# Sheet.net
KiCad netlist of a schematic drawn in Altium Designer
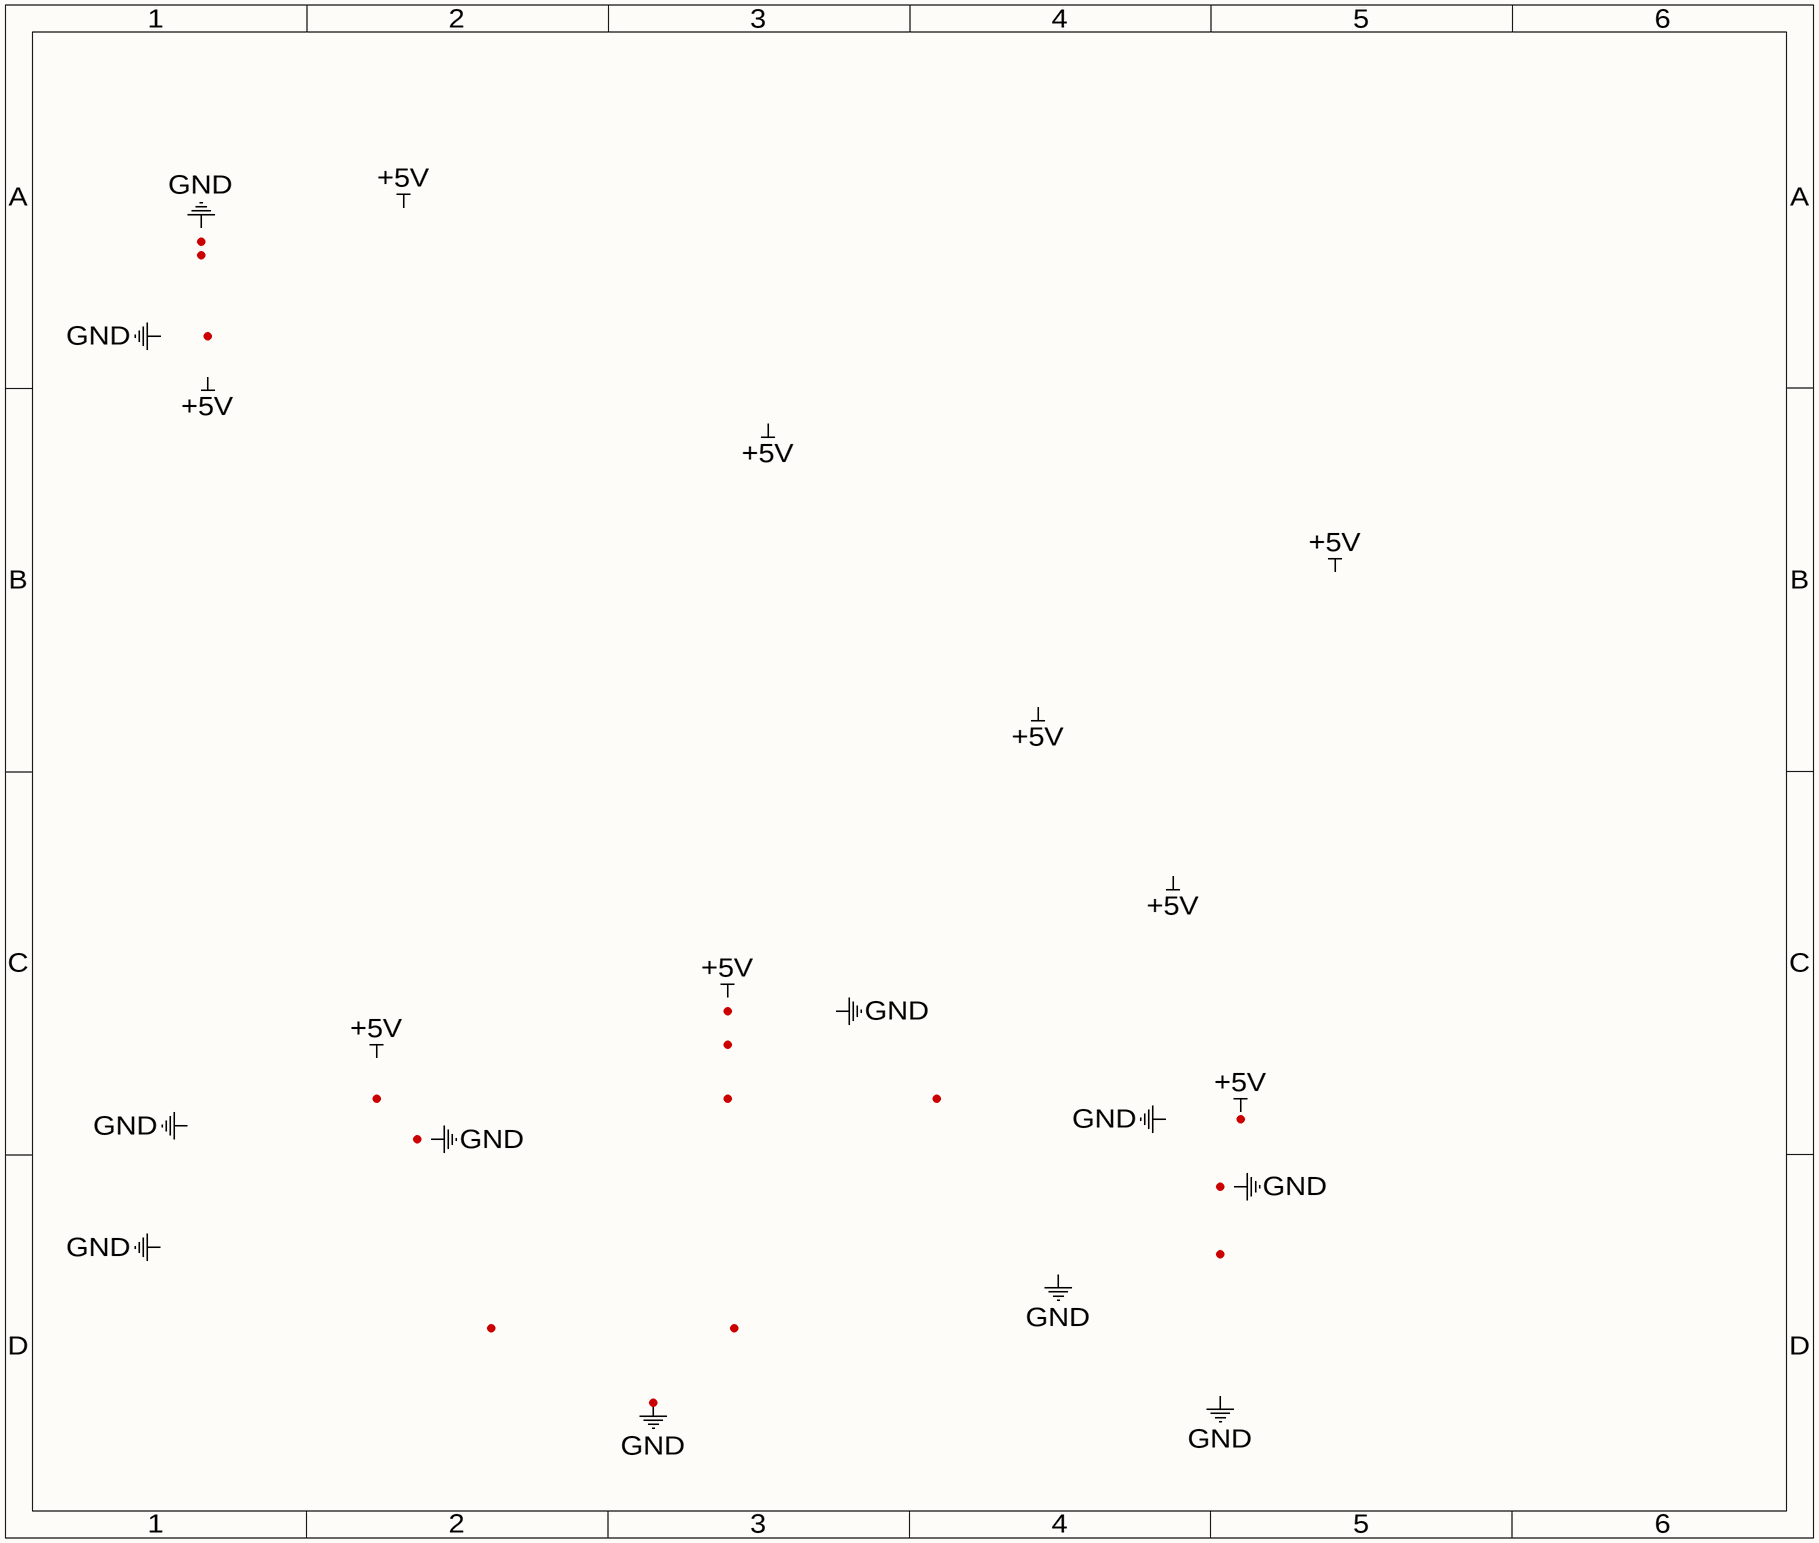
[diagram p0: Sheet.schdoc]

(export (version "E")
  (design (tool "Eeschema 10.0.6"))
  (components
    (comp (ref "BOARD1")
      (value "ESP32DEVKITV1")
      (fields (field (name "CONTRIBUTOR") "radio"))
      (libsource (lib "altium-import") (part "root_0_ESP32DEVKITV1_"))
    )
    (comp (ref "C1")
      (value "100nF")
      (fields
        (field (name "BOM_SUPPLIER PART") "C328914")
        (field (name "BOM_MANUFACTURER PART") "FN15X104K160PNG")
        (field (name "CONTRIBUTOR") "LCSC")
      )
      (libsource (lib "altium-import") (part "root_2_100nF_"))
    )
    (comp (ref "C2")
      (value "100nF")
      (fields
        (field (name "BOM_SUPPLIER PART") "C328914")
        (field (name "BOM_MANUFACTURER PART") "FN15X104K160PNG")
        (field (name "CONTRIBUTOR") "LCSC")
      )
      (libsource (lib "altium-import") (part "root_2_100nF_"))
    )
    (comp (ref "C3")
      (value "100nF")
      (fields
        (field (name "BOM_SUPPLIER PART") "C328914")
        (field (name "BOM_MANUFACTURER PART") "FN15X104K160PNG")
        (field (name "CONTRIBUTOR") "LCSC")
      )
      (libsource (lib "altium-import") (part "root_1_100nF_"))
    )
    (comp (ref "C4")
      (value "100nF")
      (fields
        (field (name "BOM_SUPPLIER PART") "C328914")
        (field (name "BOM_MANUFACTURER PART") "FN15X104K160PNG")
        (field (name "CONTRIBUTOR") "LCSC")
      )
      (libsource (lib "altium-import") (part "root_3_100nF_"))
    )
    (comp (ref "C5")
      (value "100nF")
      (fields
        (field (name "BOM_SUPPLIER PART") "C328914")
        (field (name "BOM_MANUFACTURER PART") "FN15X104K160PNG")
        (field (name "CONTRIBUTOR") "LCSC")
      )
      (libsource (lib "altium-import") (part "root_2_100nF_"))
    )
    (comp (ref "C6")
      (value "100nF")
      (fields
        (field (name "BOM_SUPPLIER PART") "C328914")
        (field (name "BOM_MANUFACTURER PART") "FN15X104K160PNG")
        (field (name "CONTRIBUTOR") "LCSC")
      )
      (libsource (lib "altium-import") (part "root_2_100nF_"))
    )
    (comp (ref "ERROR")
      (value "17-21SURC/S530-A2/TR8")
      (fields (field (name "BOM_SUPPLIER PART") "C131244") (field (name "CONTRIBUTOR") "LCSC"))
      (libsource (lib "altium-import") (part "root_1_17-21SURC/S530-A2/TR8_"))
    )
    (comp (ref "GC")
      (value "17-21SURC/S530-A2/TR8")
      (fields (field (name "BOM_SUPPLIER PART") "C131244") (field (name "CONTRIBUTOR") "LCSC"))
      (libsource (lib "altium-import") (part "root_1_17-21SURC/S530-A2/TR8_"))
    )
    (comp (ref "GL")
      (value "17-21SURC/S530-A2/TR8")
      (fields (field (name "BOM_SUPPLIER PART") "C131244") (field (name "CONTRIBUTOR") "LCSC"))
      (libsource (lib "altium-import") (part "root_1_17-21SURC/S530-A2/TR8_"))
    )
    (comp (ref "GR")
      (value "17-21SURC/S530-A2/TR8")
      (fields (field (name "BOM_SUPPLIER PART") "C131244") (field (name "CONTRIBUTOR") "LCSC"))
      (libsource (lib "altium-import") (part "root_1_17-21SURC/S530-A2/TR8_"))
    )
    (comp (ref "K1")
      (value "KH-3635-CAJ")
      (fields (field (name "BOM_SUPPLIER PART") "C530670") (field (name "CONTRIBUTOR") "LCSC"))
      (libsource (lib "altium-import") (part "root_0_KH-3635-CAJ_"))
    )
    (comp (ref "K2")
      (value "KH-3635-CAJ")
      (fields (field (name "BOM_SUPPLIER PART") "C530670") (field (name "CONTRIBUTOR") "LCSC"))
      (libsource (lib "altium-import") (part "root_0_KH-3635-CAJ_"))
    )
    (comp (ref "LED1")
      (value "17-21SYGC/S530-E3/TR8")
      (fields (field (name "BOM_SUPPLIER PART") "C142303") (field (name "CONTRIBUTOR") "LCSC"))
      (libsource (lib "altium-import") (part "root_1_17-21SYGC/S530-E3/TR8_"))
    )
    (comp (ref "OLED1")
      (value "0.96OLED_4P")
      (fields (field (name "CONTRIBUTOR") "LCEDA_Lib"))
      (libsource (lib "altium-import") (part "root_0_0.96OLED_4P_"))
    )
    (comp (ref "OPEN")
      (value "SK-3296S-01-L1")
      (fields (field (name "BOM_SUPPLIER PART") "C319020") (field (name "CONTRIBUTOR") "LCSC"))
      (libsource (lib "altium-import") (part "root_1_SK-3296S-01-L1_"))
    )
    (comp (ref "R1")
      (value "510")
      (fields
        (field (name "BOM_MANUFACTURER PART") "0603WAF1002T5E")
        (field (name "BOM_SUPPLIER PART") "C25804")
      )
      (libsource (lib "altium-import") (part "root_1_510_"))
    )
    (comp (ref "R2")
      (value "510")
      (fields
        (field (name "BOM_MANUFACTURER PART") "0603WAF1002T5E")
        (field (name "BOM_SUPPLIER PART") "C25804")
      )
      (libsource (lib "altium-import") (part "root_1_510_"))
    )
    (comp (ref "R3")
      (value "1k")
      (fields
        (field (name "BOM_MANUFACTURER PART") "0603WAF1002T5E")
        (field (name "BOM_SUPPLIER PART") "C25804")
      )
      (libsource (lib "altium-import") (part "root_0_1k_"))
    )
    (comp (ref "RC")
      (value "17-21SURC/S530-A2/TR8")
      (fields (field (name "BOM_SUPPLIER PART") "C131244") (field (name "CONTRIBUTOR") "LCSC"))
      (libsource (lib "altium-import") (part "root_1_17-21SURC/S530-A2/TR8_"))
    )
    (comp (ref "RL")
      (value "17-21SURC/S530-A2/TR8")
      (fields (field (name "BOM_SUPPLIER PART") "C131244") (field (name "CONTRIBUTOR") "LCSC"))
      (libsource (lib "altium-import") (part "root_1_17-21SURC/S530-A2/TR8_"))
    )
    (comp (ref "RN1")
      (value "470")
      (fields
        (field (name "BOM_MANUFACTURER PART") "YC164-FR-071KL")
        (field (name "BOM_SUPPLIER PART") "C110021")
      )
      (libsource (lib "altium-import") (part "root_0_470_"))
    )
    (comp (ref "RN2")
      (value "470")
      (fields
        (field (name "BOM_MANUFACTURER PART") "YC164-FR-071KL")
        (field (name "BOM_SUPPLIER PART") "C110021")
      )
      (libsource (lib "altium-import") (part "root_0_470_"))
    )
    (comp (ref "RR")
      (value "17-21SURC/S530-A2/TR8")
      (fields (field (name "BOM_SUPPLIER PART") "C131244") (field (name "CONTRIBUTOR") "LCSC"))
      (libsource (lib "altium-import") (part "root_1_17-21SURC/S530-A2/TR8_"))
    )
    (comp (ref "U1")
      (value "PCF8574T/3,518")
      (fields (field (name "BOM_SUPPLIER PART") "C7605"))
      (libsource (lib "altium-import") (part "root_0_PCF8574T/3,518_"))
    )
    (comp (ref "U2")
      (value "74HC240D,653")
      (fields (field (name "BOM_SUPPLIER PART") "C8094"))
      (libsource (lib "altium-import") (part "root_0_74HC240D,653_"))
    )
    (comp (ref "U3")
      (value "74HC30D,653")
      (fields (field (name "BOM_SUPPLIER PART") "C5631"))
      (libsource (lib "altium-import") (part "root_0_74HC30D,653_"))
    )
    (comp (ref "U4")
      (value "74HC30D,653")
      (fields (field (name "BOM_SUPPLIER PART") "C5631"))
      (libsource (lib "altium-import") (part "root_0_74HC30D,653_"))
    )
    (comp (ref "U5")
      (value "AMS1117-3.3_C347222")
      (fields
        (field (name "BOM_SUPPLIER PART") "C347222")
        (field (name "BOM_MANUFACTURER PART") "AMS1117-3.3")
        (field (name "CONTRIBUTOR") "LCSC")
      )
      (libsource (lib "altium-import") (part "root_0_AMS1117-3.3_C347222_"))
    )
    (comp (ref "U6")
      (value "74HC30D,653")
      (fields (field (name "BOM_SUPPLIER PART") "C5631"))
      (libsource (lib "altium-import") (part "root_0_74HC30D,653_"))
    )
    (comp (ref "U7")
      (value "74HC30D,653")
      (fields (field (name "BOM_SUPPLIER PART") "C5631"))
      (libsource (lib "altium-import") (part "root_0_74HC30D,653_"))
    )
    (comp (ref "U8")
      (value "74HC08D,653")
      (fields (field (name "BOM_SUPPLIER PART") "C5593"))
      (libsource (lib "altium-import") (part "root_0_74HC08D,653_"))
    )
    (comp (ref "USB1")
      (value "KH-TYPE-C-6P")
      (fields (field (name "BOM_SUPPLIER PART") "C709355") (field (name "CONTRIBUTOR") "LCSC"))
      (libsource (lib "altium-import") (part "root_0_KH-TYPE-C-6P_"))
    )
    (comp (ref "YL")
      (value "17-21SURC/S530-A2/TR8")
      (fields (field (name "BOM_SUPPLIER PART") "C131244") (field (name "CONTRIBUTOR") "LCSC"))
      (libsource (lib "altium-import") (part "root_1_17-21SURC/S530-A2/TR8_"))
    )
    (comp (ref "YR")
      (value "17-21SURC/S530-A2/TR8")
      (fields (field (name "BOM_SUPPLIER PART") "C131244") (field (name "CONTRIBUTOR") "LCSC"))
      (libsource (lib "altium-import") (part "root_1_17-21SURC/S530-A2/TR8_"))
    )
  )
  (nets
    (net (code "1") (name "+5V") (class "Default")
      (node (ref "BOARD1") (pin "VIN") (pinfunction "VIN_VIN") (pintype "passive"))
      (node (ref "C1") (pin "2") (pinfunction "2_2") (pintype "passive"))
      (node (ref "C2") (pin "1") (pinfunction "1_1") (pintype "passive"))
      (node (ref "C4") (pin "2") (pinfunction "2_2") (pintype "passive"))
      (node (ref "C5") (pin "2") (pinfunction "2_2") (pintype "passive"))
      (node (ref "C6") (pin "1") (pinfunction "1_1") (pintype "passive"))
      (node (ref "OPEN") (pin "1") (pinfunction "1_1") (pintype "passive"))
      (node (ref "R1") (pin "2") (pinfunction "2_2") (pintype "passive"))
      (node (ref "U1") (pin "16") (pinfunction "VDD_16") (pintype "passive"))
      (node (ref "U2") (pin "20") (pinfunction "VCC_20") (pintype "passive"))
      (node (ref "U3") (pin "14") (pinfunction "VCC_14") (pintype "passive"))
      (node (ref "U4") (pin "14") (pinfunction "VCC_14") (pintype "passive"))
      (node (ref "U5") (pin "3") (pinfunction "VIN_3") (pintype "passive"))
      (node (ref "U6") (pin "14") (pinfunction "VCC_14") (pintype "passive"))
      (node (ref "U7") (pin "14") (pinfunction "VCC_14") (pintype "passive"))
      (node (ref "U8") (pin "14") (pinfunction "VCC_14") (pintype "passive"))
    )
    (net (code "2") (name "/+3.3V") (class "Default")
      (node (ref "C3") (pin "1") (pinfunction "1_1") (pintype "passive"))
      (node (ref "OLED1") (pin "2") (pinfunction "2_2") (pintype "passive"))
      (node (ref "U5") (pin "2") (pinfunction "VOUT(TAB)_2") (pintype "passive"))
      (node (ref "U5") (pin "4") (pinfunction "TAB_4") (pintype "passive"))
    )
    (net (code "3") (name "/A") (class "Default")
      (node (ref "RN1") (pin "8") (pinfunction "8_8") (pintype "passive"))
      (node (ref "U1") (pin "4") (pinfunction "P0_4") (pintype "passive"))
      (node (ref "U2") (pin "2") (pinfunction "1A0_2") (pintype "passive"))
      (node (ref "U3") (pin "1") (pinfunction "A_1") (pintype "passive"))
    )
    (net (code "4") (name "/A`") (class "Default")
      (node (ref "U2") (pin "18") (pinfunction "1Y0_18") (pintype "passive"))
      (node (ref "U4") (pin "1") (pinfunction "A_1") (pintype "passive"))
      (node (ref "U6") (pin "1") (pinfunction "A_1") (pintype "passive"))
      (node (ref "U7") (pin "1") (pinfunction "A_1") (pintype "passive"))
    )
    (net (code "5") (name "/B") (class "Default")
      (node (ref "RN1") (pin "7") (pinfunction "7_7") (pintype "passive"))
      (node (ref "U1") (pin "5") (pinfunction "P1_5") (pintype "passive"))
      (node (ref "U2") (pin "4") (pinfunction "1A1_4") (pintype "passive"))
      (node (ref "U7") (pin "2") (pinfunction "B_2") (pintype "passive"))
    )
    (net (code "6") (name "/B`") (class "Default")
      (node (ref "U2") (pin "16") (pinfunction "1Y1_16") (pintype "passive"))
      (node (ref "U3") (pin "2") (pinfunction "B_2") (pintype "passive"))
      (node (ref "U4") (pin "2") (pinfunction "B_2") (pintype "passive"))
      (node (ref "U6") (pin "2") (pinfunction "B_2") (pintype "passive"))
    )
    (net (code "7") (name "/C") (class "Default")
      (node (ref "RN1") (pin "6") (pinfunction "6_6") (pintype "passive"))
      (node (ref "U1") (pin "6") (pinfunction "P2_6") (pintype "passive"))
      (node (ref "U2") (pin "6") (pinfunction "1A2_6") (pintype "passive"))
      (node (ref "U4") (pin "3") (pinfunction "C_3") (pintype "passive"))
      (node (ref "U6") (pin "3") (pinfunction "C_3") (pintype "passive"))
    )
    (net (code "8") (name "/C`") (class "Default")
      (node (ref "U2") (pin "14") (pinfunction "1Y2_14") (pintype "passive"))
      (node (ref "U3") (pin "3") (pinfunction "C_3") (pintype "passive"))
      (node (ref "U7") (pin "3") (pinfunction "C_3") (pintype "passive"))
    )
    (net (code "9") (name "/D") (class "Default")
      (node (ref "RN1") (pin "5") (pinfunction "5_5") (pintype "passive"))
      (node (ref "U1") (pin "7") (pinfunction "P3_7") (pintype "passive"))
      (node (ref "U2") (pin "8") (pinfunction "1A3_8") (pintype "passive"))
      (node (ref "U4") (pin "4") (pinfunction "D_4") (pintype "passive"))
      (node (ref "U6") (pin "4") (pinfunction "D_4") (pintype "passive"))
    )
    (net (code "10") (name "/DC") (class "Default")
      (node (ref "OPEN") (pin "2") (pinfunction "2_2") (pintype "passive"))
      (node (ref "USB1") (pin "A9") (pinfunction "VBUS_A9") (pintype "passive"))
      (node (ref "USB1") (pin "B9") (pinfunction "VBUS_B9") (pintype "passive"))
    )
    (net (code "11") (name "/D`") (class "Default")
      (node (ref "U2") (pin "12") (pinfunction "1Y3_12") (pintype "passive"))
      (node (ref "U3") (pin "4") (pinfunction "D_4") (pintype "passive"))
      (node (ref "U7") (pin "4") (pinfunction "D_4") (pintype "passive"))
    )
    (net (code "12") (name "/E") (class "Default")
      (node (ref "RN2") (pin "8") (pinfunction "8_8") (pintype "passive"))
      (node (ref "U1") (pin "9") (pinfunction "P4_9") (pintype "passive"))
      (node (ref "U2") (pin "17") (pinfunction "2A0_17") (pintype "passive"))
      (node (ref "U7") (pin "5") (pinfunction "E_5") (pintype "passive"))
    )
    (net (code "13") (name "/E`") (class "Default")
      (node (ref "U2") (pin "3") (pinfunction "2Y0_3") (pintype "passive"))
      (node (ref "U3") (pin "5") (pinfunction "E_5") (pintype "passive"))
      (node (ref "U4") (pin "5") (pinfunction "E_5") (pintype "passive"))
      (node (ref "U6") (pin "5") (pinfunction "E_5") (pintype "passive"))
    )
    (net (code "14") (name "/F") (class "Default")
      (node (ref "RN2") (pin "7") (pinfunction "7_7") (pintype "passive"))
      (node (ref "U1") (pin "10") (pinfunction "P5_10") (pintype "passive"))
      (node (ref "U2") (pin "15") (pinfunction "2A1_15") (pintype "passive"))
      (node (ref "U3") (pin "6") (pinfunction "F_6") (pintype "passive"))
    )
    (net (code "15") (name "/F`") (class "Default")
      (node (ref "U2") (pin "5") (pinfunction "2Y1_5") (pintype "passive"))
      (node (ref "U4") (pin "6") (pinfunction "F_6") (pintype "passive"))
      (node (ref "U6") (pin "6") (pinfunction "F_6") (pintype "passive"))
      (node (ref "U7") (pin "6") (pinfunction "F_6") (pintype "passive"))
    )
    (net (code "16") (name "/G") (class "Default")
      (node (ref "RN2") (pin "6") (pinfunction "6_6") (pintype "passive"))
      (node (ref "U1") (pin "11") (pinfunction "P6_11") (pintype "passive"))
      (node (ref "U2") (pin "13") (pinfunction "2A2_13") (pintype "passive"))
      (node (ref "U3") (pin "11") (pinfunction "G_11") (pintype "passive"))
      (node (ref "U4") (pin "11") (pinfunction "G_11") (pintype "passive"))
      (node (ref "U7") (pin "11") (pinfunction "G_11") (pintype "passive"))
    )
    (net (code "17") (name "/G`") (class "Default")
      (node (ref "U2") (pin "7") (pinfunction "2Y2_7") (pintype "passive"))
      (node (ref "U6") (pin "11") (pinfunction "G_11") (pintype "passive"))
    )
    (net (code "18") (name "/H") (class "Default")
      (node (ref "RN2") (pin "5") (pinfunction "5_5") (pintype "passive"))
      (node (ref "U1") (pin "12") (pinfunction "P7_12") (pintype "passive"))
      (node (ref "U2") (pin "11") (pinfunction "2A3_11") (pintype "passive"))
      (node (ref "U6") (pin "12") (pinfunction "H_12") (pintype "passive"))
    )
    (net (code "19") (name "/H`") (class "Default")
      (node (ref "U2") (pin "9") (pinfunction "2Y3_9") (pintype "passive"))
      (node (ref "U3") (pin "12") (pinfunction "H_12") (pintype "passive"))
      (node (ref "U4") (pin "12") (pinfunction "H_12") (pintype "passive"))
      (node (ref "U7") (pin "12") (pinfunction "H_12") (pintype "passive"))
    )
    (net (code "20") (name "/K1") (class "Default")
      (node (ref "BOARD1") (pin "D17") (pinfunction "D17_D17") (pintype "passive"))
      (node (ref "K1") (pin "1") (pinfunction "C_1") (pintype "passive"))
    )
    (net (code "21") (name "/K2") (class "Default")
      (node (ref "BOARD1") (pin "D16") (pinfunction "D16_D16") (pintype "passive"))
      (node (ref "K2") (pin "1") (pinfunction "C_1") (pintype "passive"))
    )
    (net (code "22") (name "/OLED_SCL") (class "Default")
      (node (ref "BOARD1") (pin "D23") (pinfunction "D23_D23") (pintype "passive"))
      (node (ref "OLED1") (pin "3") (pinfunction "3_3") (pintype "passive"))
    )
    (net (code "23") (name "/OLED_SDA") (class "Default")
      (node (ref "BOARD1") (pin "D22") (pinfunction "D22_D22") (pintype "passive"))
      (node (ref "OLED1") (pin "4") (pinfunction "4_4") (pintype "passive"))
    )
    (net (code "24") (name "/SCL") (class "Default")
      (node (ref "BOARD1") (pin "D19") (pinfunction "D19_D19") (pintype "passive"))
      (node (ref "U1") (pin "14") (pinfunction "SCL_14") (pintype "passive"))
    )
    (net (code "25") (name "/SDA") (class "Default")
      (node (ref "BOARD1") (pin "D18") (pinfunction "D18_D18") (pintype "passive"))
      (node (ref "U1") (pin "15") (pinfunction "SDA_15") (pintype "passive"))
    )
    (net (code "26") (name "/Y") (class "Default")
      (node (ref "R2") (pin "2") (pinfunction "2_2") (pintype "passive"))
      (node (ref "R3") (pin "2") (pinfunction "2_2") (pintype "passive"))
      (node (ref "U8") (pin "8") (pinfunction "3Y_8") (pintype "passive"))
    )
    (net (code "27") (name "/Y1") (class "Default")
      (node (ref "U3") (pin "8") (pinfunction "Y_8") (pintype "passive"))
      (node (ref "U8") (pin "1") (pinfunction "1A_1") (pintype "passive"))
    )
    (net (code "28") (name "/Y2") (class "Default")
      (node (ref "U4") (pin "8") (pinfunction "Y_8") (pintype "passive"))
      (node (ref "U8") (pin "2") (pinfunction "1B_2") (pintype "passive"))
    )
    (net (code "29") (name "/Y3") (class "Default")
      (node (ref "U6") (pin "8") (pinfunction "Y_8") (pintype "passive"))
      (node (ref "U8") (pin "5") (pinfunction "2B_5") (pintype "passive"))
    )
    (net (code "30") (name "/Y4") (class "Default")
      (node (ref "U7") (pin "8") (pinfunction "Y_8") (pintype "passive"))
      (node (ref "U8") (pin "10") (pinfunction "3B_10") (pintype "passive"))
    )
    (net (code "31") (name "GND") (class "Default")
      (node (ref "BOARD1") (pin "GND") (pinfunction "GND_GND") (pintype "passive"))
      (node (ref "BOARD1") (pin "GND@1") (pinfunction "GND_GND@1") (pintype "passive"))
      (node (ref "C1") (pin "1") (pinfunction "1_1") (pintype "passive"))
      (node (ref "C2") (pin "2") (pinfunction "2_2") (pintype "passive"))
      (node (ref "C3") (pin "2") (pinfunction "2_2") (pintype "passive"))
      (node (ref "C4") (pin "1") (pinfunction "1_1") (pintype "passive"))
      (node (ref "C5") (pin "1") (pinfunction "1_1") (pintype "passive"))
      (node (ref "C6") (pin "2") (pinfunction "2_2") (pintype "passive"))
      (node (ref "ERROR") (pin "1") (pinfunction "K_1") (pintype "passive"))
      (node (ref "GC") (pin "1") (pinfunction "K_1") (pintype "passive"))
      (node (ref "GL") (pin "1") (pinfunction "K_1") (pintype "passive"))
      (node (ref "GR") (pin "1") (pinfunction "K_1") (pintype "passive"))
      (node (ref "K1") (pin "2") (pinfunction "D_2") (pintype "passive"))
      (node (ref "K1") (pin "4") (pinfunction "B_4") (pintype "passive"))
      (node (ref "K2") (pin "2") (pinfunction "D_2") (pintype "passive"))
      (node (ref "K2") (pin "4") (pinfunction "B_4") (pintype "passive"))
      (node (ref "LED1") (pin "1") (pinfunction "K_1") (pintype "passive"))
      (node (ref "OLED1") (pin "1") (pinfunction "1_1") (pintype "passive"))
      (node (ref "RC") (pin "1") (pinfunction "K_1") (pintype "passive"))
      (node (ref "RL") (pin "1") (pinfunction "K_1") (pintype "passive"))
      (node (ref "RR") (pin "1") (pinfunction "K_1") (pintype "passive"))
      (node (ref "U1") (pin "1") (pinfunction "A0_1") (pintype "passive"))
      (node (ref "U1") (pin "2") (pinfunction "A1_2") (pintype "passive"))
      (node (ref "U1") (pin "3") (pinfunction "A2_3") (pintype "passive"))
      (node (ref "U1") (pin "8") (pinfunction "VSS_8") (pintype "passive"))
      (node (ref "U2") (pin "1") (pinfunction "1OE#_1") (pintype "passive"))
      (node (ref "U2") (pin "10") (pinfunction "GND_10") (pintype "passive"))
      (node (ref "U2") (pin "19") (pinfunction "2OE#_19") (pintype "passive"))
      (node (ref "U3") (pin "7") (pinfunction "GND_7") (pintype "passive"))
      (node (ref "U4") (pin "7") (pinfunction "GND_7") (pintype "passive"))
      (node (ref "U5") (pin "1") (pinfunction "ADJ(GND)_1") (pintype "passive"))
      (node (ref "U6") (pin "7") (pinfunction "GND_7") (pintype "passive"))
      (node (ref "U7") (pin "7") (pinfunction "GND_7") (pintype "passive"))
      (node (ref "U8") (pin "12") (pinfunction "4A_12") (pintype "passive"))
      (node (ref "U8") (pin "13") (pinfunction "4B_13") (pintype "passive"))
      (node (ref "U8") (pin "7") (pinfunction "GND_7") (pintype "passive"))
      (node (ref "USB1") (pin "1") (pinfunction "EP_1") (pintype "passive"))
      (node (ref "USB1") (pin "2") (pinfunction "EP_2") (pintype "passive"))
      (node (ref "USB1") (pin "3") (pinfunction "EP_3") (pintype "passive"))
      (node (ref "USB1") (pin "4") (pinfunction "EP_4") (pintype "passive"))
      (node (ref "USB1") (pin "A12") (pinfunction "GND_A12") (pintype "passive"))
      (node (ref "USB1") (pin "B12") (pinfunction "GND_B12") (pintype "passive"))
      (node (ref "YL") (pin "1") (pinfunction "K_1") (pintype "passive"))
      (node (ref "YR") (pin "1") (pinfunction "K_1") (pintype "passive"))
    )
    (net (code "32") (name "Net-(BOARD1-PadD15)") (class "Default")
      (node (ref "BOARD1") (pin "D15") (pinfunction "D15_D15") (pintype "passive"))
      (node (ref "R3") (pin "1") (pinfunction "1_1") (pintype "passive"))
    )
    (net (code "33") (name "Net-(ERROR-A)") (class "Default")
      (node (ref "ERROR") (pin "2") (pinfunction "A_2") (pintype "passive"))
      (node (ref "R2") (pin "1") (pinfunction "1_1") (pintype "passive"))
    )
    (net (code "34") (name "Net-(GC-A)") (class "Default")
      (node (ref "GC") (pin "2") (pinfunction "A_2") (pintype "passive"))
      (node (ref "RN2") (pin "4") (pinfunction "4_4") (pintype "passive"))
    )
    (net (code "35") (name "Net-(GL-A)") (class "Default")
      (node (ref "GL") (pin "2") (pinfunction "A_2") (pintype "passive"))
      (node (ref "RN1") (pin "3") (pinfunction "3_3") (pintype "passive"))
    )
    (net (code "36") (name "Net-(GR-A)") (class "Default")
      (node (ref "GR") (pin "2") (pinfunction "A_2") (pintype "passive"))
      (node (ref "RN2") (pin "2") (pinfunction "2_2") (pintype "passive"))
    )
    (net (code "37") (name "Net-(LED1-A)") (class "Default")
      (node (ref "LED1") (pin "2") (pinfunction "A_2") (pintype "passive"))
      (node (ref "R1") (pin "1") (pinfunction "1_1") (pintype "passive"))
    )
    (net (code "38") (name "Net-(RC-A)") (class "Default")
      (node (ref "RC") (pin "2") (pinfunction "A_2") (pintype "passive"))
      (node (ref "RN2") (pin "3") (pinfunction "3_3") (pintype "passive"))
    )
    (net (code "39") (name "Net-(RL-A)") (class "Default")
      (node (ref "RL") (pin "2") (pinfunction "A_2") (pintype "passive"))
      (node (ref "RN1") (pin "1") (pinfunction "1_1") (pintype "passive"))
    )
    (net (code "40") (name "Net-(RR-A)") (class "Default")
      (node (ref "RN1") (pin "4") (pinfunction "4_4") (pintype "passive"))
      (node (ref "RR") (pin "2") (pinfunction "A_2") (pintype "passive"))
    )
    (net (code "41") (name "Net-(U8-1Y)") (class "Default")
      (node (ref "U8") (pin "3") (pinfunction "1Y_3") (pintype "passive"))
      (node (ref "U8") (pin "4") (pinfunction "2A_4") (pintype "passive"))
    )
    (net (code "42") (name "Net-(U8-2Y)") (class "Default")
      (node (ref "U8") (pin "6") (pinfunction "2Y_6") (pintype "passive"))
      (node (ref "U8") (pin "9") (pinfunction "3A_9") (pintype "passive"))
    )
    (net (code "43") (name "Net-(YL-A)") (class "Default")
      (node (ref "RN1") (pin "2") (pinfunction "2_2") (pintype "passive"))
      (node (ref "YL") (pin "2") (pinfunction "A_2") (pintype "passive"))
    )
    (net (code "44") (name "Net-(YR-A)") (class "Default")
      (node (ref "RN2") (pin "1") (pinfunction "1_1") (pintype "passive"))
      (node (ref "YR") (pin "2") (pinfunction "A_2") (pintype "passive"))
    )
    (net (code "45") (name "unconnected-(BOARD1-Pad3V3)") (class "Default")
      (node (ref "BOARD1") (pin "3V3") (pinfunction "3V3_3V3") (pintype "passive"))
    )
    (net (code "46") (name "unconnected-(BOARD1-PadD1)") (class "Default")
      (node (ref "BOARD1") (pin "D1") (pinfunction "D1_D1") (pintype "passive"))
    )
    (net (code "47") (name "unconnected-(BOARD1-PadD2)") (class "Default")
      (node (ref "BOARD1") (pin "D2") (pinfunction "D2_D2") (pintype "passive"))
    )
    (net (code "48") (name "unconnected-(BOARD1-PadD3)") (class "Default")
      (node (ref "BOARD1") (pin "D3") (pinfunction "D3_D3") (pintype "passive"))
    )
    (net (code "49") (name "unconnected-(BOARD1-PadD4)") (class "Default")
      (node (ref "BOARD1") (pin "D4") (pinfunction "D4_D4") (pintype "passive"))
    )
    (net (code "50") (name "unconnected-(BOARD1-PadD5)") (class "Default")
      (node (ref "BOARD1") (pin "D5") (pinfunction "D5_D5") (pintype "passive"))
    )
    (net (code "51") (name "unconnected-(BOARD1-PadD12)") (class "Default")
      (node (ref "BOARD1") (pin "D12") (pinfunction "D12_D12") (pintype "passive"))
    )
    (net (code "52") (name "unconnected-(BOARD1-PadD13)") (class "Default")
      (node (ref "BOARD1") (pin "D13") (pinfunction "D13_D13") (pintype "passive"))
    )
    (net (code "53") (name "unconnected-(BOARD1-PadD14)") (class "Default")
      (node (ref "BOARD1") (pin "D14") (pinfunction "D14_D14") (pintype "passive"))
    )
    (net (code "54") (name "unconnected-(BOARD1-PadD21)") (class "Default")
      (node (ref "BOARD1") (pin "D21") (pinfunction "D21_D21") (pintype "passive"))
    )
    (net (code "55") (name "unconnected-(BOARD1-PadD25)") (class "Default")
      (node (ref "BOARD1") (pin "D25") (pinfunction "D25_D25") (pintype "passive"))
    )
    (net (code "56") (name "unconnected-(BOARD1-PadD26)") (class "Default")
      (node (ref "BOARD1") (pin "D26") (pinfunction "D26_D26") (pintype "passive"))
    )
    (net (code "57") (name "unconnected-(BOARD1-PadD27)") (class "Default")
      (node (ref "BOARD1") (pin "D27") (pinfunction "D27_D27") (pintype "passive"))
    )
    (net (code "58") (name "unconnected-(BOARD1-PadD32)") (class "Default")
      (node (ref "BOARD1") (pin "D32") (pinfunction "D32_D32") (pintype "passive"))
    )
    (net (code "59") (name "unconnected-(BOARD1-PadD33)") (class "Default")
      (node (ref "BOARD1") (pin "D33") (pinfunction "D33_D33") (pintype "passive"))
    )
    (net (code "60") (name "unconnected-(BOARD1-PadD34)") (class "Default")
      (node (ref "BOARD1") (pin "D34") (pinfunction "D34_D34") (pintype "passive"))
    )
    (net (code "61") (name "unconnected-(BOARD1-PadD35)") (class "Default")
      (node (ref "BOARD1") (pin "D35") (pinfunction "D35_D35") (pintype "passive"))
    )
    (net (code "62") (name "unconnected-(BOARD1-PadEN)") (class "Default")
      (node (ref "BOARD1") (pin "EN") (pinfunction "EN_EN") (pintype "passive"))
    )
    (net (code "63") (name "unconnected-(BOARD1-PadVN)") (class "Default")
      (node (ref "BOARD1") (pin "VN") (pinfunction "VN_VN") (pintype "passive"))
    )
    (net (code "64") (name "unconnected-(BOARD1-PadVP)") (class "Default")
      (node (ref "BOARD1") (pin "VP") (pinfunction "VP_VP") (pintype "passive"))
    )
    (net (code "65") (name "unconnected-(K1-A-Pad3)") (class "Default")
      (node (ref "K1") (pin "3") (pinfunction "A_3") (pintype "passive"))
    )
    (net (code "66") (name "unconnected-(K2-A-Pad3)") (class "Default")
      (node (ref "K2") (pin "3") (pinfunction "A_3") (pintype "passive"))
    )
    (net (code "67") (name "unconnected-(OPEN-Pad0)") (class "Default")
      (node (ref "OPEN") (pin "0") (pinfunction "0_0") (pintype "passive"))
    )
    (net (code "68") (name "unconnected-(OPEN-Pad3)") (class "Default")
      (node (ref "OPEN") (pin "3") (pinfunction "3_3") (pintype "passive"))
    )
    (net (code "69") (name "unconnected-(U1-INT#-Pad13)") (class "Default")
      (node (ref "U1") (pin "13") (pinfunction "INT#_13") (pintype "passive"))
    )
    (net (code "70") (name "unconnected-(U3-N.C.-Pad9)") (class "Default")
      (node (ref "U3") (pin "9") (pinfunction "N.C._9") (pintype "passive"))
    )
    (net (code "71") (name "unconnected-(U3-N.C.{slash}2-Pad13)") (class "Default")
      (node (ref "U3") (pin "13") (pinfunction "N.C./2_13") (pintype "passive"))
    )
    (net (code "72") (name "unconnected-(U3-N.C.{slash}3-Pad10)") (class "Default")
      (node (ref "U3") (pin "10") (pinfunction "N.C./3_10") (pintype "passive"))
    )
    (net (code "73") (name "unconnected-(U4-N.C.-Pad9)") (class "Default")
      (node (ref "U4") (pin "9") (pinfunction "N.C._9") (pintype "passive"))
    )
    (net (code "74") (name "unconnected-(U4-N.C.{slash}2-Pad13)") (class "Default")
      (node (ref "U4") (pin "13") (pinfunction "N.C./2_13") (pintype "passive"))
    )
    (net (code "75") (name "unconnected-(U4-N.C.{slash}3-Pad10)") (class "Default")
      (node (ref "U4") (pin "10") (pinfunction "N.C./3_10") (pintype "passive"))
    )
    (net (code "76") (name "unconnected-(U6-N.C.-Pad9)") (class "Default")
      (node (ref "U6") (pin "9") (pinfunction "N.C._9") (pintype "passive"))
    )
    (net (code "77") (name "unconnected-(U6-N.C.{slash}2-Pad13)") (class "Default")
      (node (ref "U6") (pin "13") (pinfunction "N.C./2_13") (pintype "passive"))
    )
    (net (code "78") (name "unconnected-(U6-N.C.{slash}3-Pad10)") (class "Default")
      (node (ref "U6") (pin "10") (pinfunction "N.C./3_10") (pintype "passive"))
    )
    (net (code "79") (name "unconnected-(U7-N.C.-Pad9)") (class "Default")
      (node (ref "U7") (pin "9") (pinfunction "N.C._9") (pintype "passive"))
    )
    (net (code "80") (name "unconnected-(U7-N.C.{slash}2-Pad13)") (class "Default")
      (node (ref "U7") (pin "13") (pinfunction "N.C./2_13") (pintype "passive"))
    )
    (net (code "81") (name "unconnected-(U7-N.C.{slash}3-Pad10)") (class "Default")
      (node (ref "U7") (pin "10") (pinfunction "N.C./3_10") (pintype "passive"))
    )
    (net (code "82") (name "unconnected-(U8-4Y-Pad11)") (class "Default")
      (node (ref "U8") (pin "11") (pinfunction "4Y_11") (pintype "passive"))
    )
    (net (code "83") (name "unconnected-(USB1-CC1-PadA5)") (class "Default")
      (node (ref "USB1") (pin "A5") (pinfunction "CC1_A5") (pintype "passive"))
    )
    (net (code "84") (name "unconnected-(USB1-CC2-PadB5)") (class "Default")
      (node (ref "USB1") (pin "B5") (pinfunction "CC2_B5") (pintype "passive"))
    )
  )
)
